# EM2050.net
KiCad netlist of a schematic drawn in Altium Designer
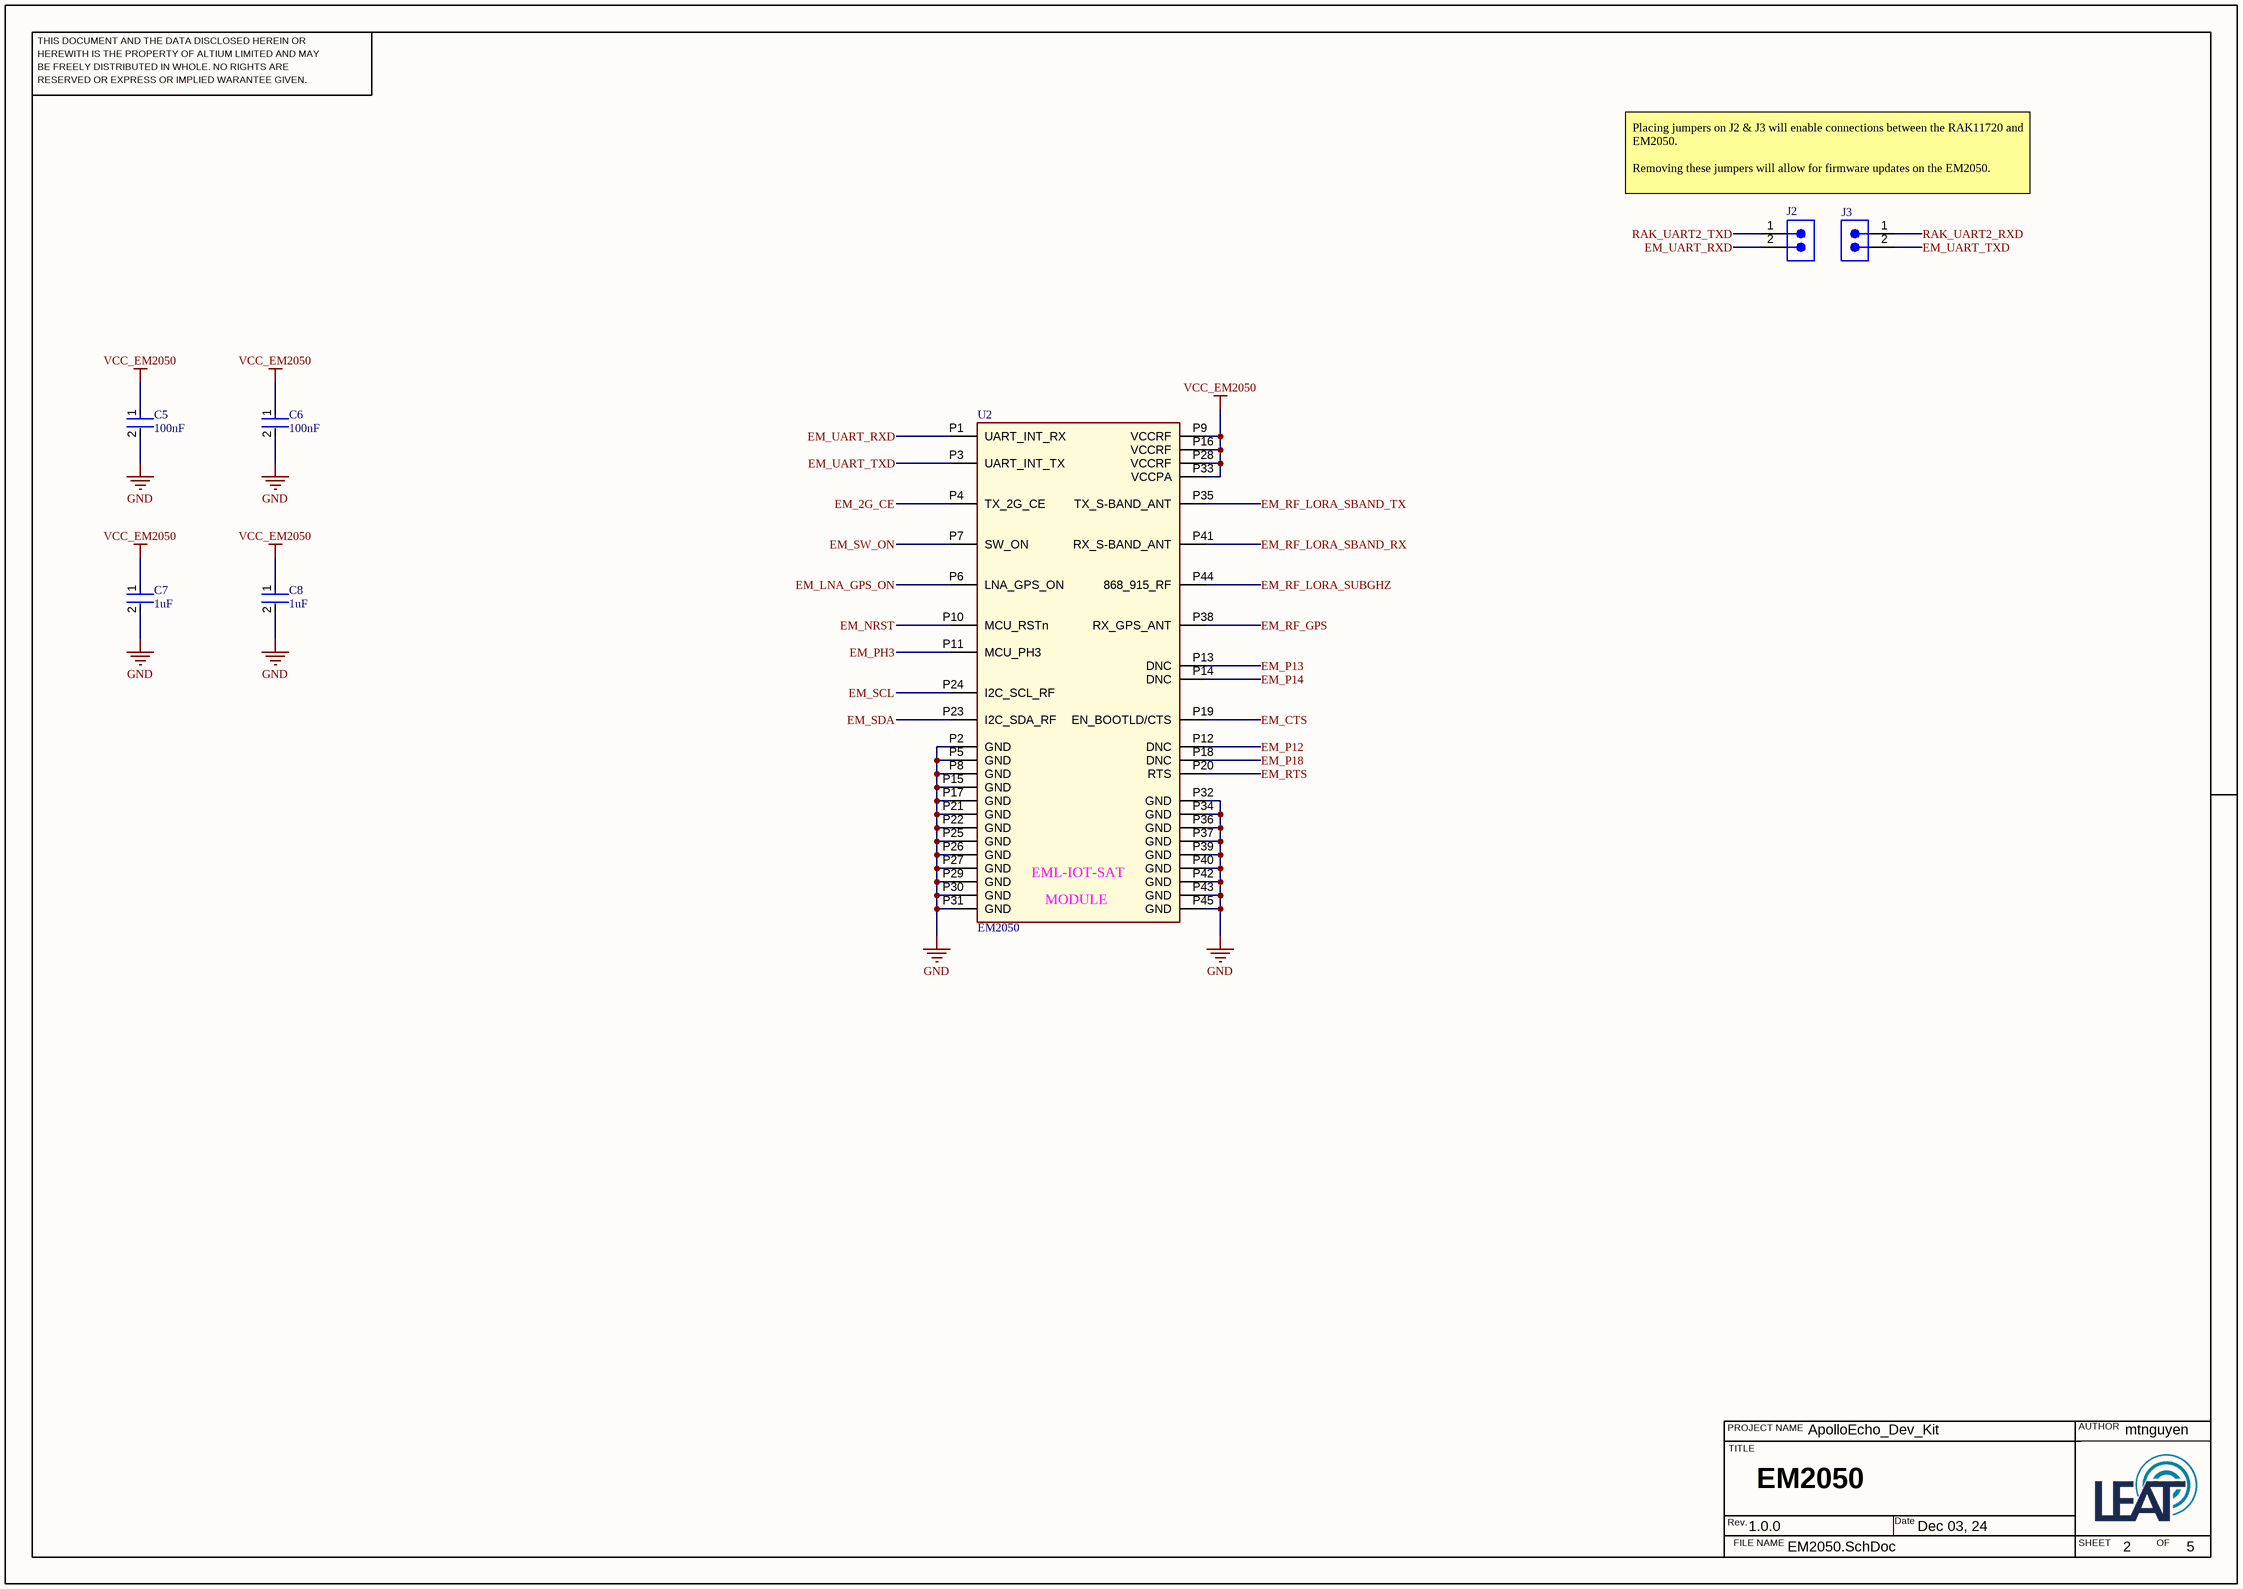
[diagram p0: EM2050.SchDoc]

(export (version "E")
  (design (tool "Eeschema 10.0.6"))
  (components
    (comp (ref "C5")
      (value "0402ZD104KAT2A")
      (footprint "FP-0402-L_1_0_1-W_0_5_0_1-IPC_C")
      (description "General Purpose Ceramic Capacitor, 0402, 100nF, 10%, X5R, 15%, 10V")
      (fields
        (field (name "VOLTAGE") "10V")
        (field (name "TOLERANCE") "10%")
        (field (name "CAPACITANCE") "100nF")
      )
      (libsource (lib "Altium Content Vault") (part "b4654b650e69147ec39a6b967a45e02"))
    )
    (comp (ref "C6")
      (value "0402ZD104KAT2A")
      (footprint "FP-0402-L_1_0_1-W_0_5_0_1-IPC_C")
      (description "General Purpose Ceramic Capacitor, 0402, 100nF, 10%, X5R, 15%, 10V")
      (fields
        (field (name "VOLTAGE") "10V")
        (field (name "TOLERANCE") "10%")
        (field (name "CAPACITANCE") "100nF")
      )
      (libsource (lib "Altium Content Vault") (part "b4654b650e69147ec39a6b967a45e02"))
    )
    (comp (ref "C7")
      (value "EMK105BJ105KV-F")
      (footprint "FP-0402-L_1_0_0_05-W_0_5-IPC_A")
      (description "None")
      (fields (field (name "TOLERANCE") "10%") (field (name "CAPACITANCE") "1uF"))
      (libsource (lib "Altium Content Vault") (part "b4654b650e69147ec39a6b967a45e02"))
    )
    (comp (ref "C8")
      (value "EMK105BJ105KV-F")
      (footprint "FP-0402-L_1_0_0_05-W_0_5-IPC_A")
      (description "None")
      (fields (field (name "TOLERANCE") "10%") (field (name "CAPACITANCE") "1uF"))
      (libsource (lib "Altium Content Vault") (part "b4654b650e69147ec39a6b967a45e02"))
    )
    (comp (ref "J2")
      (value "61300211121")
      (footprint "61300211121")
      (libsource (lib "Altium Content Vault") (part "Header_Male_1R_02P"))
    )
    (comp (ref "J3")
      (value "61300211121")
      (footprint "61300211121")
      (libsource (lib "Altium Content Vault") (part "Header_Male_1R_02P"))
    )
    (comp (ref "U2")
      (value "EM2050")
      (footprint "EM2050")
      (description "Echostar Mobile IOT SAT Module - Basic version")
      (fields (field (name "MANUFACTURER") "Echostar Mobile Ltd") (field (name "Comment") "IOT SAT module"))
      (libsource (lib "EchoStar") (part "EM2050"))
    )
  )
  (nets
    (net (code "1") (name "/EM_2G_CE") (class "Default")
      (node (ref "U2") (pin "P4") (pinfunction "TX_2G_CE_P4") (pintype "passive"))
    )
    (net (code "2") (name "/EM_CTS") (class "Default")
      (node (ref "U2") (pin "P19") (pinfunction "EN_BOOTLD/CTS_P19") (pintype "passive"))
    )
    (net (code "3") (name "/EM_LNA_GPS_ON") (class "Default")
      (node (ref "U2") (pin "P6") (pinfunction "LNA_GPS_ON_P6") (pintype "passive"))
    )
    (net (code "4") (name "/EM_NRST") (class "Default")
      (node (ref "U2") (pin "P10") (pinfunction "MCU_RSTn_P10") (pintype "passive"))
    )
    (net (code "5") (name "/EM_P12") (class "Default")
      (node (ref "U2") (pin "P12") (pinfunction "DNC_P12") (pintype "passive"))
    )
    (net (code "6") (name "/EM_P13") (class "Default")
      (node (ref "U2") (pin "P13") (pinfunction "DNC_P13") (pintype "passive"))
    )
    (net (code "7") (name "/EM_P14") (class "Default")
      (node (ref "U2") (pin "P14") (pinfunction "DNC_P14") (pintype "passive"))
    )
    (net (code "8") (name "/EM_P18") (class "Default")
      (node (ref "U2") (pin "P18") (pinfunction "DNC_P18") (pintype "passive"))
    )
    (net (code "9") (name "/EM_PH3") (class "Default")
      (node (ref "U2") (pin "P11") (pinfunction "MCU_PH3_P11") (pintype "passive"))
    )
    (net (code "10") (name "/EM_RF_GPS") (class "Default")
      (node (ref "U2") (pin "P38") (pinfunction "RX_GPS_ANT_P38") (pintype "passive"))
    )
    (net (code "11") (name "/EM_RF_LORA_SBAND_RX") (class "Default")
      (node (ref "U2") (pin "P41") (pinfunction "RX_S-BAND_ANT_P41") (pintype "passive"))
    )
    (net (code "12") (name "/EM_RF_LORA_SBAND_TX") (class "Default")
      (node (ref "U2") (pin "P35") (pinfunction "TX_S-BAND_ANT_P35") (pintype "passive"))
    )
    (net (code "13") (name "/EM_RF_LORA_SUBGHZ") (class "Default")
      (node (ref "U2") (pin "P44") (pinfunction "868_915_RF_P44") (pintype "passive"))
    )
    (net (code "14") (name "/EM_RTS") (class "Default")
      (node (ref "U2") (pin "P20") (pinfunction "RTS_P20") (pintype "passive"))
    )
    (net (code "15") (name "/EM_SCL") (class "Default")
      (node (ref "U2") (pin "P24") (pinfunction "I2C_SCL_RF_P24") (pintype "passive"))
    )
    (net (code "16") (name "/EM_SDA") (class "Default")
      (node (ref "U2") (pin "P23") (pinfunction "I2C_SDA_RF_P23") (pintype "passive"))
    )
    (net (code "17") (name "/EM_SW_ON") (class "Default")
      (node (ref "U2") (pin "P7") (pinfunction "SW_ON_P7") (pintype "passive"))
    )
    (net (code "18") (name "/EM_UART_RXD") (class "Default")
      (node (ref "J2") (pin "2") (pinfunction "2_2") (pintype "passive"))
      (node (ref "U2") (pin "P1") (pinfunction "UART_INT_RX_P1") (pintype "passive"))
    )
    (net (code "19") (name "/EM_UART_TXD") (class "Default")
      (node (ref "J3") (pin "2") (pinfunction "2_2") (pintype "passive"))
      (node (ref "U2") (pin "P3") (pinfunction "UART_INT_TX_P3") (pintype "passive"))
    )
    (net (code "20") (name "/RAK_UART2_RXD") (class "Default")
      (node (ref "J3") (pin "1") (pinfunction "1_1") (pintype "passive"))
    )
    (net (code "21") (name "/RAK_UART2_TXD") (class "Default")
      (node (ref "J2") (pin "1") (pinfunction "1_1") (pintype "passive"))
    )
    (net (code "22") (name "GND") (class "Default")
      (node (ref "C5") (pin "2") (pinfunction "2_2") (pintype "passive"))
      (node (ref "C6") (pin "2") (pinfunction "2_2") (pintype "passive"))
      (node (ref "C7") (pin "2") (pinfunction "2_2") (pintype "passive"))
      (node (ref "C8") (pin "2") (pinfunction "2_2") (pintype "passive"))
      (node (ref "U2") (pin "P15") (pinfunction "GND_P15") (pintype "passive"))
      (node (ref "U2") (pin "P17") (pinfunction "GND_P17") (pintype "passive"))
      (node (ref "U2") (pin "P2") (pinfunction "GND_P2") (pintype "passive"))
      (node (ref "U2") (pin "P21") (pinfunction "GND_P21") (pintype "passive"))
      (node (ref "U2") (pin "P22") (pinfunction "GND_P22") (pintype "passive"))
      (node (ref "U2") (pin "P25") (pinfunction "GND_P25") (pintype "passive"))
      (node (ref "U2") (pin "P26") (pinfunction "GND_P26") (pintype "passive"))
      (node (ref "U2") (pin "P27") (pinfunction "GND_P27") (pintype "passive"))
      (node (ref "U2") (pin "P29") (pinfunction "GND_P29") (pintype "passive"))
      (node (ref "U2") (pin "P30") (pinfunction "GND_P30") (pintype "passive"))
      (node (ref "U2") (pin "P31") (pinfunction "GND_P31") (pintype "passive"))
      (node (ref "U2") (pin "P32") (pinfunction "GND_P32") (pintype "passive"))
      (node (ref "U2") (pin "P34") (pinfunction "GND_P34") (pintype "passive"))
      (node (ref "U2") (pin "P36") (pinfunction "GND_P36") (pintype "passive"))
      (node (ref "U2") (pin "P37") (pinfunction "GND_P37") (pintype "passive"))
      (node (ref "U2") (pin "P39") (pinfunction "GND_P39") (pintype "passive"))
      (node (ref "U2") (pin "P40") (pinfunction "GND_P40") (pintype "passive"))
      (node (ref "U2") (pin "P42") (pinfunction "GND_P42") (pintype "passive"))
      (node (ref "U2") (pin "P43") (pinfunction "GND_P43") (pintype "passive"))
      (node (ref "U2") (pin "P45") (pinfunction "GND_P45") (pintype "passive"))
      (node (ref "U2") (pin "P5") (pinfunction "GND_P5") (pintype "passive"))
      (node (ref "U2") (pin "P8") (pinfunction "GND_P8") (pintype "passive"))
    )
    (net (code "23") (name "VCC_EM2050") (class "Default")
      (node (ref "C5") (pin "1") (pinfunction "1_1") (pintype "passive"))
      (node (ref "C6") (pin "1") (pinfunction "1_1") (pintype "passive"))
      (node (ref "C7") (pin "1") (pinfunction "1_1") (pintype "passive"))
      (node (ref "C8") (pin "1") (pinfunction "1_1") (pintype "passive"))
      (node (ref "U2") (pin "P16") (pinfunction "VCCRF_P16") (pintype "passive"))
      (node (ref "U2") (pin "P28") (pinfunction "VCCRF_P28") (pintype "passive"))
      (node (ref "U2") (pin "P33") (pinfunction "VCCPA_P33") (pintype "passive"))
      (node (ref "U2") (pin "P9") (pinfunction "VCCRF_P9") (pintype "passive"))
    )
  )
)
